# 13-GPRS.net
KiCad netlist of a schematic drawn in Altium Designer
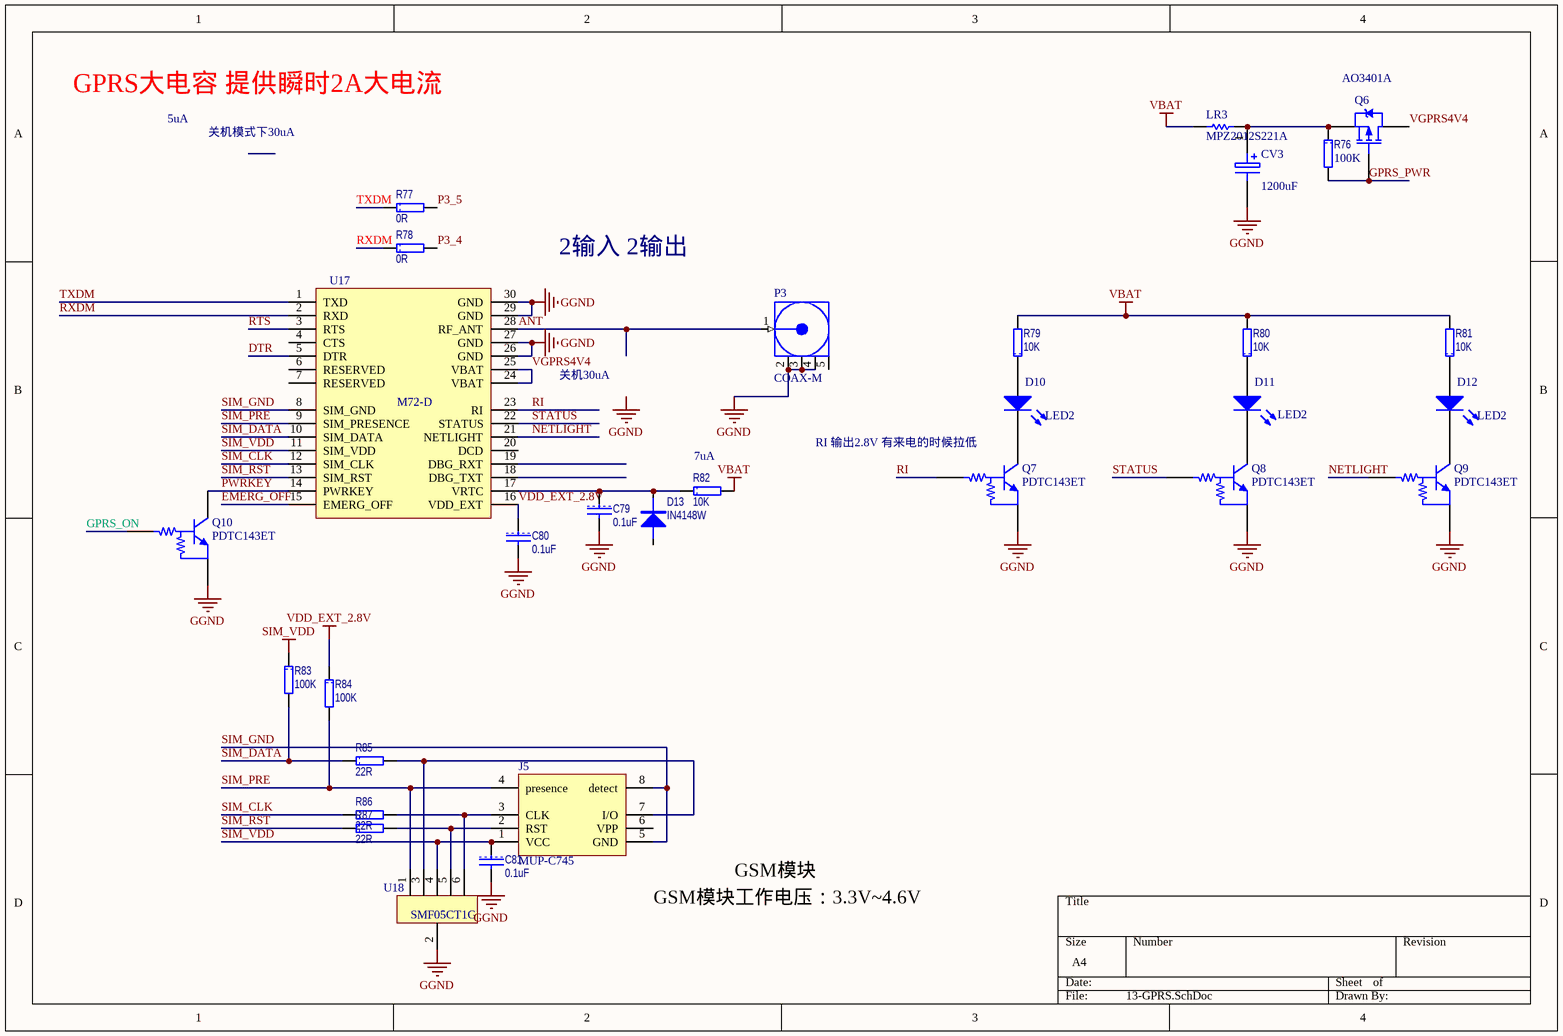
[diagram p0: 13-GPRS.SchDoc]

(export (version "E")
  (design (tool "Eeschema 10.0.6"))
  (components
    (comp (ref "C79")
      (value "0.1uF")
      (footprint "1608[0603]")
      (description "Capacitor")
      (fields (field (name "MANUFACTURER") "TDK"))
      (libsource (lib "*") (part "CAP"))
    )
    (comp (ref "C80")
      (value "0.1uF")
      (footprint "1608[0603]")
      (description "Capacitor")
      (fields (field (name "MANUFACTURER") "TDK"))
      (libsource (lib "*") (part "CAP"))
    )
    (comp (ref "C81")
      (value "0.1uF")
      (footprint "1608[0603]")
      (description "Capacitor")
      (fields (field (name "MANUFACTURER") "TDK"))
      (libsource (lib "*") (part "CAP"))
    )
    (comp (ref "CV3")
      (value "1200uF")
      (footprint "CAPPR5-10x20/H1.1")
      (description "插针 铝质电解电容器 - 带引线 1200uF 10V")
      (fields
        (field (name "MANUFACTURER") "Panasonic Electronic Components")
        (field (name "MANUFACTURER PART NUMBER") "EEU-FC1A122")
      )
      (libsource (lib "*") (part "ELECTRO1"))
    )
    (comp (ref "D10")
      (value "LED2")
      (footprint "0805LED")
      (description "Typical RED, GREEN, YELLOW, AMBER GaAs LED")
      (fields (field (name "PUBLISHER") "Altium Limited"))
      (libsource (lib "Miscellaneous Devices") (part "LED2"))
    )
    (comp (ref "D11")
      (value "LED2")
      (footprint "0805LED")
      (description "Typical RED, GREEN, YELLOW, AMBER GaAs LED")
      (fields (field (name "PUBLISHER") "Altium Limited"))
      (libsource (lib "Miscellaneous Devices") (part "LED2"))
    )
    (comp (ref "D12")
      (value "LED2")
      (footprint "0805LED")
      (description "Typical RED, GREEN, YELLOW, AMBER GaAs LED")
      (fields (field (name "PUBLISHER") "Altium Limited"))
      (libsource (lib "Miscellaneous Devices") (part "LED2"))
    )
    (comp (ref "D13")
      (value "IN4148W")
      (footprint "SOD123")
      (description "DIODE")
      (libsource (lib "*") (part "DIODE"))
    )
    (comp (ref "J5")
      (value "MUP-C745")
      (footprint "MUP-C745")
      (description "CON")
      (libsource (lib "*") (part "SIMCARD"))
    )
    (comp (ref "LR3")
      (value "MPZ2012S221A")
      (footprint "2012[0805]")
      (description "电磁干扰滤波珠子、扼流圈和阵列 Ferrite Chip Beads")
      (fields (field (name "MANUFACTURER") "TDK"))
      (libsource (lib "Miscellaneous Devices") (part "Res Semi"))
    )
    (comp (ref "P3")
      (value "COAX-M")
      (footprint "MHF[MCB3]-V4")
      (description "RF Coaxial PCB Connector, MMCX; Thru-Hole, Vertical Mount Plug,  50 Ohm Impedance")
      (fields (field (name "PUBLISHER") "Altium Limited"))
      (libsource (lib "Miscellaneous Connectors") (part "COAX-M"))
    )
    (comp (ref "Q6")
      (value "AO3401A")
      (footprint "SOT23_N")
      (description "MOSFET P-CH -30V -4.3A SOT23")
      (fields (field (name "MANUFACTURER") "Alpha & Omega Semiconductor Inc"))
      (libsource (lib "IR Discrete MOSFET - Power") (part "IRLML5103"))
    )
    (comp (ref "Q7")
      (value "PDTC143ET")
      (footprint "SOT23_N")
      (description "NPN Resistor-equipped Transistor")
      (fields (field (name "PUBLISHER") "Altium Limited"))
      (libsource (lib "Philips Discrete BJT - Low Power") (part "PDTC143ET"))
    )
    (comp (ref "Q8")
      (value "PDTC143ET")
      (footprint "SOT23_N")
      (description "NPN Resistor-equipped Transistor")
      (fields (field (name "PUBLISHER") "Altium Limited"))
      (libsource (lib "Philips Discrete BJT - Low Power") (part "PDTC143ET"))
    )
    (comp (ref "Q9")
      (value "PDTC143ET")
      (footprint "SOT23_N")
      (description "NPN Resistor-equipped Transistor")
      (fields (field (name "PUBLISHER") "Altium Limited"))
      (libsource (lib "Philips Discrete BJT - Low Power") (part "PDTC143ET"))
    )
    (comp (ref "Q10")
      (value "PDTC143ET")
      (footprint "SOT23_N")
      (description "NPN Resistor-equipped Transistor")
      (fields (field (name "PUBLISHER") "Altium Limited"))
      (libsource (lib "Philips Discrete BJT - Low Power") (part "PDTC143ET"))
    )
    (comp (ref "R76")
      (value "100K")
      (footprint "1608[0603]R")
      (description "厚膜电阻器 - SMD 1/10watt 100Kohms 1%")
      (fields
        (field (name "MANUFACTURER") "Vishay / Dale")
        (field (name "MANUFACTURER PART NUMBER") "CRCW0603100KFKEA")
      )
      (libsource (lib "100K 1%") (part "RES"))
    )
    (comp (ref "R77")
      (value "0R")
      (footprint "1608[0603]R")
      (description "RES")
      (libsource (lib "*") (part "RES"))
    )
    (comp (ref "R78")
      (value "0R")
      (footprint "1608[0603]R")
      (description "RES")
      (libsource (lib "*") (part "RES"))
    )
    (comp (ref "R79")
      (value "10K")
      (footprint "1608[0603]R")
      (description "RES")
      (libsource (lib "*") (part "RES"))
    )
    (comp (ref "R80")
      (value "10K")
      (footprint "1608[0603]R")
      (description "RES")
      (libsource (lib "*") (part "RES"))
    )
    (comp (ref "R81")
      (value "10K")
      (footprint "1608[0603]R")
      (description "RES")
      (libsource (lib "*") (part "RES"))
    )
    (comp (ref "R82")
      (value "10K")
      (footprint "1608[0603]R")
      (description "RES")
      (libsource (lib "*") (part "RES"))
    )
    (comp (ref "R83")
      (value "100K")
      (footprint "1608[0603]R")
      (description "RES")
      (libsource (lib "*") (part "RES"))
    )
    (comp (ref "R84")
      (value "100K")
      (footprint "1608[0603]R")
      (description "RES")
      (libsource (lib "*") (part "RES"))
    )
    (comp (ref "R85")
      (value "22R")
      (footprint "1608[0603]R")
      (description "RES")
      (libsource (lib "*") (part "RES"))
    )
    (comp (ref "R86")
      (value "22R")
      (footprint "1608[0603]R")
      (description "RES")
      (libsource (lib "*") (part "RES"))
    )
    (comp (ref "R87")
      (value "22R")
      (footprint "1608[0603]R")
      (description "RES")
      (libsource (lib "*") (part "RES"))
    )
    (comp (ref "U17")
      (value "M72-D")
      (footprint "M72D")
      (description "GSM模块")
      (libsource (lib "*") (part "M72-D"))
    )
    (comp (ref "U18")
      (value "SMF05CT1G")
      (footprint "SOT23-6_N")
      (description "ESD")
      (libsource (lib "*") (part "SMF05CT1G"))
    )
  )
  (nets
    (net (code "1") (name "/ANT") (class "Default")
      (node (ref "P3") (pin "1") (pinfunction "Signal_1") (pintype "input"))
      (node (ref "U17") (pin "28") (pinfunction "RF_ANT_28") (pintype "passive"))
    )
    (net (code "2") (name "/DTR") (class "Default")
      (node (ref "U17") (pin "5") (pinfunction "DTR_5") (pintype "passive"))
    )
    (net (code "3") (name "/EMERG_OFF") (class "Default")
      (node (ref "U17") (pin "15") (pinfunction "EMERG_OFF_15") (pintype "passive"))
    )
    (net (code "4") (name "/GPRS_ON") (class "Default")
      (node (ref "Q10") (pin "1") (pinfunction "B_1") (pintype "passive"))
    )
    (net (code "5") (name "/GPRS_PWR") (class "Default")
      (node (ref "Q6") (pin "1") (pinfunction "G_1") (pintype "passive"))
      (node (ref "R76") (pin "2") (pinfunction "2_2") (pintype "passive"))
    )
    (net (code "6") (name "/NETLIGHT") (class "Default")
      (node (ref "Q9") (pin "1") (pinfunction "B_1") (pintype "passive"))
      (node (ref "U17") (pin "21") (pinfunction "NETLIGHT_21") (pintype "passive"))
    )
    (net (code "7") (name "/P3_4") (class "Default")
      (node (ref "R78") (pin "2") (pinfunction "2_2") (pintype "passive"))
    )
    (net (code "8") (name "/P3_5") (class "Default")
      (node (ref "R77") (pin "2") (pinfunction "2_2") (pintype "passive"))
    )
    (net (code "9") (name "/PWRKEY") (class "Default")
      (node (ref "Q10") (pin "3") (pinfunction "C_3") (pintype "passive"))
      (node (ref "U17") (pin "14") (pinfunction "PWRKEY_14") (pintype "passive"))
    )
    (net (code "10") (name "/RI") (class "Default")
      (node (ref "Q7") (pin "1") (pinfunction "B_1") (pintype "passive"))
      (node (ref "U17") (pin "23") (pinfunction "RI_23") (pintype "passive"))
    )
    (net (code "11") (name "/RTS") (class "Default")
      (node (ref "U17") (pin "3") (pinfunction "RTS_3") (pintype "passive"))
    )
    (net (code "12") (name "/RXDM") (class "Default")
      (node (ref "R78") (pin "1") (pinfunction "1_1") (pintype "passive"))
      (node (ref "U17") (pin "2") (pinfunction "RXD_2") (pintype "passive"))
    )
    (net (code "13") (name "/SIM_CLK") (class "Default")
      (node (ref "R86") (pin "1") (pinfunction "1_1") (pintype "passive"))
      (node (ref "U17") (pin "12") (pinfunction "SIM_CLK_12") (pintype "passive"))
    )
    (net (code "14") (name "/SIM_DATA") (class "Default")
      (node (ref "R83") (pin "2") (pinfunction "2_2") (pintype "passive"))
      (node (ref "R85") (pin "1") (pinfunction "1_1") (pintype "passive"))
      (node (ref "U17") (pin "10") (pinfunction "SIM_DATA_10") (pintype "passive"))
    )
    (net (code "15") (name "/SIM_GND") (class "Default")
      (node (ref "J5") (pin "5") (pinfunction "GND_5") (pintype "passive"))
      (node (ref "J5") (pin "8") (pinfunction "detect_8") (pintype "passive"))
      (node (ref "U17") (pin "8") (pinfunction "SIM_GND_8") (pintype "passive"))
    )
    (net (code "16") (name "/SIM_PRE") (class "Default")
      (node (ref "J5") (pin "4") (pinfunction "presence_4") (pintype "passive"))
      (node (ref "R84") (pin "2") (pinfunction "2_2") (pintype "passive"))
      (node (ref "U17") (pin "9") (pinfunction "SIM_PRESENCE_9") (pintype "passive"))
      (node (ref "U18") (pin "1") (pinfunction "1_1") (pintype "passive"))
    )
    (net (code "17") (name "/SIM_RST") (class "Default")
      (node (ref "R87") (pin "1") (pinfunction "1_1") (pintype "passive"))
      (node (ref "U17") (pin "13") (pinfunction "SIM_RST_13") (pintype "passive"))
    )
    (net (code "18") (name "/STATUS") (class "Default")
      (node (ref "Q8") (pin "1") (pinfunction "B_1") (pintype "passive"))
      (node (ref "U17") (pin "22") (pinfunction "STATUS_22") (pintype "passive"))
    )
    (net (code "19") (name "/TXDM") (class "Default")
      (node (ref "R77") (pin "1") (pinfunction "1_1") (pintype "passive"))
      (node (ref "U17") (pin "1") (pinfunction "TXD_1") (pintype "passive"))
    )
    (net (code "20") (name "/VGPRS4V4") (class "Default")
      (node (ref "Q6") (pin "3") (pinfunction "D_3") (pintype "passive"))
      (node (ref "U17") (pin "24") (pinfunction "VBAT_24") (pintype "passive"))
      (node (ref "U17") (pin "25") (pinfunction "VBAT_25") (pintype "passive"))
    )
    (net (code "21") (name "GGND") (class "Default")
      (node (ref "C79") (pin "2") (pinfunction "2_2") (pintype "passive"))
      (node (ref "C80") (pin "2") (pinfunction "2_2") (pintype "passive"))
      (node (ref "C81") (pin "2") (pinfunction "2_2") (pintype "passive"))
      (node (ref "CV3") (pin "2") (pinfunction "2_2") (pintype "passive"))
      (node (ref "P3") (pin "2") (pinfunction "GND_2") (pintype "power_in"))
      (node (ref "P3") (pin "3") (pinfunction "GND_3") (pintype "power_in"))
      (node (ref "P3") (pin "4") (pinfunction "GND_4") (pintype "power_in"))
      (node (ref "Q10") (pin "2") (pinfunction "E_2") (pintype "passive"))
      (node (ref "Q7") (pin "2") (pinfunction "E_2") (pintype "passive"))
      (node (ref "Q8") (pin "2") (pinfunction "E_2") (pintype "passive"))
      (node (ref "Q9") (pin "2") (pinfunction "E_2") (pintype "passive"))
      (node (ref "U17") (pin "26") (pinfunction "GND_26") (pintype "passive"))
      (node (ref "U17") (pin "27") (pinfunction "GND_27") (pintype "passive"))
      (node (ref "U17") (pin "29") (pinfunction "GND_29") (pintype "passive"))
      (node (ref "U17") (pin "30") (pinfunction "GND_30") (pintype "passive"))
      (node (ref "U18") (pin "2") (pinfunction "2_2") (pintype "passive"))
    )
    (net (code "22") (name "Net-(D10-A)") (class "Default")
      (node (ref "D10") (pin "1") (pinfunction "A_1") (pintype "passive"))
      (node (ref "R79") (pin "1") (pinfunction "1_1") (pintype "passive"))
    )
    (net (code "23") (name "Net-(D10-K)") (class "Default")
      (node (ref "D10") (pin "2") (pinfunction "K_2") (pintype "passive"))
      (node (ref "Q7") (pin "3") (pinfunction "C_3") (pintype "passive"))
    )
    (net (code "24") (name "Net-(D11-A)") (class "Default")
      (node (ref "D11") (pin "1") (pinfunction "A_1") (pintype "passive"))
      (node (ref "R80") (pin "1") (pinfunction "1_1") (pintype "passive"))
    )
    (net (code "25") (name "Net-(D11-K)") (class "Default")
      (node (ref "D11") (pin "2") (pinfunction "K_2") (pintype "passive"))
      (node (ref "Q8") (pin "3") (pinfunction "C_3") (pintype "passive"))
    )
    (net (code "26") (name "Net-(D12-A)") (class "Default")
      (node (ref "D12") (pin "1") (pinfunction "A_1") (pintype "passive"))
      (node (ref "R81") (pin "1") (pinfunction "1_1") (pintype "passive"))
    )
    (net (code "27") (name "Net-(D12-K)") (class "Default")
      (node (ref "D12") (pin "2") (pinfunction "K_2") (pintype "passive"))
      (node (ref "Q9") (pin "3") (pinfunction "C_3") (pintype "passive"))
    )
    (net (code "28") (name "Net-(J5-CLK)") (class "Default")
      (node (ref "J5") (pin "3") (pinfunction "CLK_3") (pintype "passive"))
      (node (ref "R86") (pin "2") (pinfunction "2_2") (pintype "passive"))
      (node (ref "U18") (pin "6") (pinfunction "6_6") (pintype "passive"))
    )
    (net (code "29") (name "Net-(J5-I{slash}O)") (class "Default")
      (node (ref "J5") (pin "7") (pinfunction "I/O_7") (pintype "passive"))
      (node (ref "R85") (pin "2") (pinfunction "2_2") (pintype "passive"))
      (node (ref "U18") (pin "3") (pinfunction "3_3") (pintype "passive"))
    )
    (net (code "30") (name "Net-(J5-RST)") (class "Default")
      (node (ref "J5") (pin "2") (pinfunction "RST_2") (pintype "passive"))
      (node (ref "R87") (pin "2") (pinfunction "2_2") (pintype "passive"))
      (node (ref "U18") (pin "5") (pinfunction "5_5") (pintype "passive"))
    )
    (net (code "31") (name "Net-(Q6-S)") (class "Default")
      (node (ref "CV3") (pin "1") (pinfunction "1_1") (pintype "passive"))
      (node (ref "LR3") (pin "2") (pinfunction "2_2") (pintype "passive"))
      (node (ref "Q6") (pin "2") (pinfunction "S_2") (pintype "passive"))
      (node (ref "R76") (pin "1") (pinfunction "1_1") (pintype "passive"))
    )
    (net (code "32") (name "Net-(U17-VRTC)") (class "Default")
      (node (ref "C79") (pin "1") (pinfunction "1_1") (pintype "passive"))
      (node (ref "D13") (pin "2") (pinfunction "2_2") (pintype "passive"))
      (node (ref "R82") (pin "1") (pinfunction "1_1") (pintype "passive"))
      (node (ref "U17") (pin "17") (pinfunction "VRTC_17") (pintype "passive"))
    )
    (net (code "33") (name "SIM_VDD") (class "Default")
      (node (ref "C81") (pin "1") (pinfunction "1_1") (pintype "passive"))
      (node (ref "J5") (pin "1") (pinfunction "VCC_1") (pintype "passive"))
      (node (ref "R83") (pin "1") (pinfunction "1_1") (pintype "passive"))
      (node (ref "U17") (pin "11") (pinfunction "SIM_VDD_11") (pintype "passive"))
      (node (ref "U18") (pin "4") (pinfunction "4_4") (pintype "passive"))
    )
    (net (code "34") (name "VBAT") (class "Default")
      (node (ref "LR3") (pin "1") (pinfunction "1_1") (pintype "passive"))
      (node (ref "R79") (pin "2") (pinfunction "2_2") (pintype "passive"))
      (node (ref "R80") (pin "2") (pinfunction "2_2") (pintype "passive"))
      (node (ref "R81") (pin "2") (pinfunction "2_2") (pintype "passive"))
      (node (ref "R82") (pin "2") (pinfunction "2_2") (pintype "passive"))
    )
    (net (code "35") (name "VDD_EXT_2.8V") (class "Default")
      (node (ref "C80") (pin "1") (pinfunction "1_1") (pintype "passive"))
      (node (ref "R84") (pin "1") (pinfunction "1_1") (pintype "passive"))
      (node (ref "U17") (pin "16") (pinfunction "VDD_EXT_16") (pintype "passive"))
    )
    (net (code "36") (name "unconnected-(D13-Pad1)") (class "Default")
      (node (ref "D13") (pin "1") (pinfunction "1_1") (pintype "passive"))
    )
    (net (code "37") (name "unconnected-(J5-VPP-Pad6)") (class "Default")
      (node (ref "J5") (pin "6") (pinfunction "VPP_6") (pintype "passive"))
    )
    (net (code "38") (name "unconnected-(P3-GND-Pad5)") (class "Default")
      (node (ref "P3") (pin "5") (pinfunction "GND_5") (pintype "power_in"))
    )
    (net (code "39") (name "unconnected-(U17-CTS-Pad4)") (class "Default")
      (node (ref "U17") (pin "4") (pinfunction "CTS_4") (pintype "passive"))
    )
    (net (code "40") (name "unconnected-(U17-DBG_RXT-Pad19)") (class "Default")
      (node (ref "U17") (pin "19") (pinfunction "DBG_RXT_19") (pintype "passive"))
    )
    (net (code "41") (name "unconnected-(U17-DBG_TXT-Pad18)") (class "Default")
      (node (ref "U17") (pin "18") (pinfunction "DBG_TXT_18") (pintype "passive"))
    )
    (net (code "42") (name "unconnected-(U17-DCD-Pad20)") (class "Default")
      (node (ref "U17") (pin "20") (pinfunction "DCD_20") (pintype "passive"))
    )
    (net (code "43") (name "unconnected-(U17-RESERVED-Pad6)") (class "Default")
      (node (ref "U17") (pin "6") (pinfunction "RESERVED_6") (pintype "passive"))
    )
    (net (code "44") (name "unconnected-(U17-RESERVED-Pad7)") (class "Default")
      (node (ref "U17") (pin "7") (pinfunction "RESERVED_7") (pintype "passive"))
    )
  )
)
